# EDU_High-Speed-Design_CPU_HDMI.net
KiCad netlist of a schematic drawn in Altium Designer
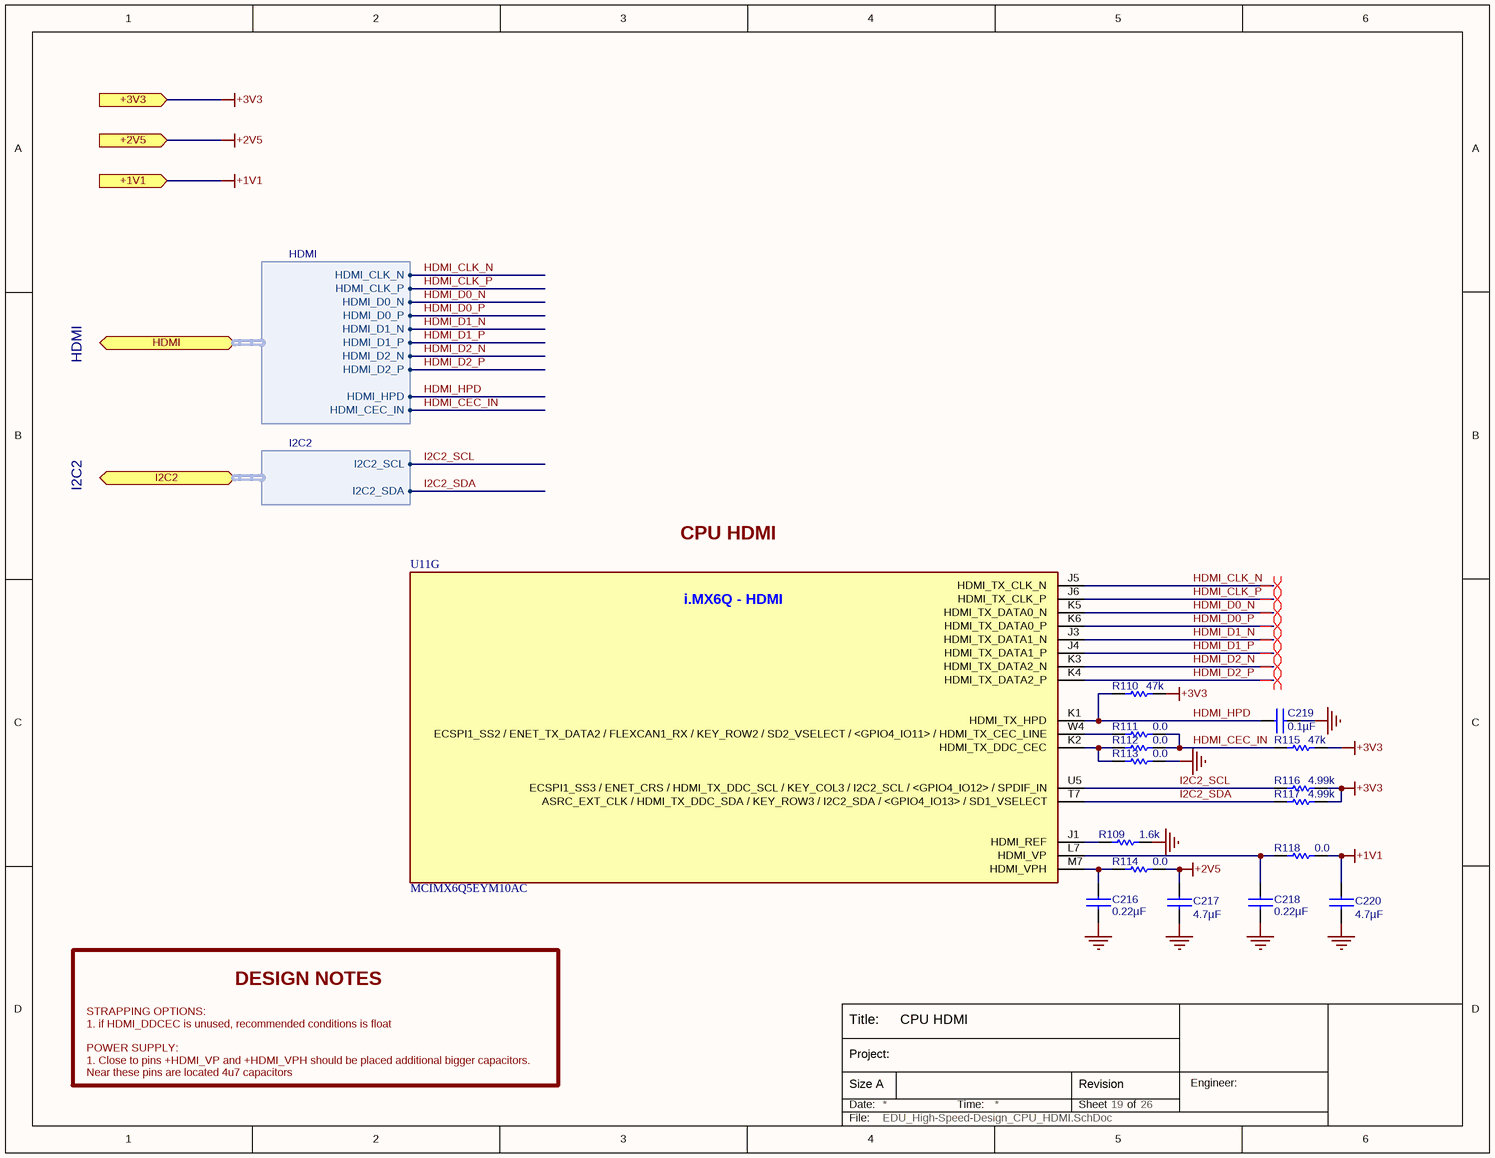
[diagram p0: EDU_High-Speed-Design_CPU_HDMI.SchDoc]

(export (version "E")
  (design (tool "Eeschema 10.0.6"))
  (components
    (comp (ref "C216")
      (value "0.22µF")
      (footprint "C0402")
      (description "CAP CER .22UF 25V X5R 20% 0402")
      (fields (field (name "VOLTAGE") "25V"))
      (libsource (lib "EDU_High-Speed-Design") (part "C1005X5R1E224M"))
    )
    (comp (ref "C217")
      (value "4.7µF")
      (footprint "C0402")
      (description "CAP CER 4.7UF 10V 20% X5R 0402")
      (fields (field (name "VOLTAGE") "10V"))
      (libsource (lib "EDU_High-Speed-Design") (part "C1005X5R1A475M"))
    )
    (comp (ref "C218")
      (value "0.22µF")
      (footprint "C0402")
      (description "CAP CER .22UF 25V X5R 20% 0402")
      (fields (field (name "VOLTAGE") "25V"))
      (libsource (lib "EDU_High-Speed-Design") (part "C1005X5R1E224M"))
    )
    (comp (ref "C219")
      (value "0.1µF")
      (footprint "C0402")
      (description "CAP CER .10UF 50V X5R 10% 0402")
      (fields (field (name "VOLTAGE") "50V"))
      (libsource (lib "EDU_High-Speed-Design") (part "C1005X5R1H104K"))
    )
    (comp (ref "C220")
      (value "4.7µF")
      (footprint "C0402")
      (description "CAP CER 4.7UF 10V 20% X5R 0402")
      (fields (field (name "VOLTAGE") "10V"))
      (libsource (lib "EDU_High-Speed-Design") (part "C1005X5R1A475M"))
    )
    (comp (ref "R109")
      (value "1.6k")
      (footprint "R0402")
      (description "RES 1.6K OHM 1/10W 1% 0402 SMD")
      (libsource (lib "EDU_High-Speed-Design") (part "ERJ-2RKF1601X"))
    )
    (comp (ref "R110")
      (value "47k")
      (footprint "R0402")
      (description "RES 47.0K OHM 1/16W 1% 0402 SMD")
      (fields
        (field (name "MANUFACTURER") "Yageo")
        (field (name "MANUFACTURER PART NUMBER") "RC0402FR-0747KL")
      )
      (libsource (lib "EDU_High-Speed-Design") (part "RC0402FR-0747KL"))
    )
    (comp (ref "R111")
      (value "0.0")
      (footprint "R0402")
      (description "RES 0.0 OHM 1/16W 0402 SMD")
      (libsource (lib "EDU_High-Speed-Design") (part "RC0402JR-070RL"))
    )
    (comp (ref "R112")
      (value "0.0")
      (footprint "R0402")
      (description "RES 0.0 OHM 1/16W 0402 SMD")
      (libsource (lib "EDU_High-Speed-Design") (part "RC0402JR-070RL"))
    )
    (comp (ref "R113")
      (value "0.0")
      (footprint "R0402")
      (description "RES 0.0 OHM 1/16W 0402 SMD")
      (libsource (lib "EDU_High-Speed-Design") (part "RC0402JR-070RL"))
    )
    (comp (ref "R114")
      (value "0.0")
      (footprint "R0402")
      (description "RES 0.0 OHM 1/16W 0402 SMD")
      (libsource (lib "EDU_High-Speed-Design") (part "RC0402JR-070RL"))
    )
    (comp (ref "R115")
      (value "47k")
      (footprint "R0402")
      (description "RES 47.0K OHM 1/16W 1% 0402 SMD")
      (fields
        (field (name "MANUFACTURER") "Yageo")
        (field (name "MANUFACTURER PART NUMBER") "RC0402FR-0747KL")
      )
      (libsource (lib "EDU_High-Speed-Design") (part "RC0402FR-0747KL"))
    )
    (comp (ref "R116")
      (value "4.99k")
      (footprint "R0402")
      (description "RES TF 4.99K OHM 1% 1/16W 0402")
      (libsource (lib "EDU_High-Speed-Design") (part "RMCF0402FT4K99"))
    )
    (comp (ref "R117")
      (value "4.99k")
      (footprint "R0402")
      (description "RES TF 4.99K OHM 1% 1/16W 0402")
      (libsource (lib "EDU_High-Speed-Design") (part "RMCF0402FT4K99"))
    )
    (comp (ref "R118")
      (value "0.0")
      (footprint "R0402")
      (description "RES 0.0 OHM 1/16W 0402 SMD")
      (libsource (lib "EDU_High-Speed-Design") (part "RC0402JR-070RL"))
    )
    (comp (ref "U11")
      (value "MCIMX6Q5EYM10AC")
      (footprint "MCIMX6Q5EYM10AC")
      (description "IC MCU 32BIT ARM QUAD 624FCBGA")
      (libsource (lib "EDU_High-Speed-Design") (part "MCIMX6Q5EYM10AC"))
    )
  )
  (nets
    (net (code "3") (name "+1V1") (class "Default")
      (node (ref "C220") (pin "1") (pinfunction "1_1") (pintype "passive"))
      (node (ref "R118") (pin "2") (pinfunction "2_2") (pintype "passive"))
    )
    (net (code "4") (name "+2V5") (class "Default")
      (node (ref "C217") (pin "1") (pinfunction "1_1") (pintype "passive"))
      (node (ref "R114") (pin "2") (pinfunction "2_2") (pintype "passive"))
    )
    (net (code "5") (name "+3V3") (class "Default")
      (node (ref "R110") (pin "1") (pinfunction "1_1") (pintype "passive"))
      (node (ref "R115") (pin "1") (pinfunction "1_1") (pintype "passive"))
      (node (ref "R116") (pin "1") (pinfunction "1_1") (pintype "passive"))
      (node (ref "R117") (pin "1") (pinfunction "1_1") (pintype "passive"))
    )
    (net (code "6") (name "/HDMI_CEC_IN") (class "Default")
      (node (ref "R111") (pin "1") (pinfunction "1_1") (pintype "passive"))
      (node (ref "R112") (pin "1") (pinfunction "1_1") (pintype "passive"))
      (node (ref "R115") (pin "2") (pinfunction "2_2") (pintype "passive"))
    )
    (net (code "7") (name "/HDMI_CLK_N") (class "Default")
      (node (ref "U11") (pin "J5") (pinfunction "HDMI_TX_CLK_N_J5") (pintype "passive"))
    )
    (net (code "8") (name "/HDMI_CLK_P") (class "Default")
      (node (ref "U11") (pin "J6") (pinfunction "HDMI_TX_CLK_P_J6") (pintype "passive"))
    )
    (net (code "9") (name "/HDMI_D0_N") (class "Default")
      (node (ref "U11") (pin "K5") (pinfunction "HDMI_TX_DATA0_N_K5") (pintype "passive"))
    )
    (net (code "10") (name "/HDMI_D0_P") (class "Default")
      (node (ref "U11") (pin "K6") (pinfunction "HDMI_TX_DATA0_P_K6") (pintype "passive"))
    )
    (net (code "11") (name "/HDMI_D1_N") (class "Default")
      (node (ref "U11") (pin "J3") (pinfunction "HDMI_TX_DATA1_N_J3") (pintype "passive"))
    )
    (net (code "12") (name "/HDMI_D1_P") (class "Default")
      (node (ref "U11") (pin "J4") (pinfunction "HDMI_TX_DATA1_P_J4") (pintype "passive"))
    )
    (net (code "13") (name "/HDMI_D2_N") (class "Default")
      (node (ref "U11") (pin "K3") (pinfunction "HDMI_TX_DATA2_N_K3") (pintype "passive"))
    )
    (net (code "14") (name "/HDMI_D2_P") (class "Default")
      (node (ref "U11") (pin "K4") (pinfunction "HDMI_TX_DATA2_P_K4") (pintype "passive"))
    )
    (net (code "15") (name "/HDMI_HPD") (class "Default")
      (node (ref "C219") (pin "1") (pinfunction "1_1") (pintype "passive"))
      (node (ref "R110") (pin "2") (pinfunction "2_2") (pintype "passive"))
      (node (ref "U11") (pin "K1") (pinfunction "HDMI_TX_HPD_K1") (pintype "passive"))
    )
    (net (code "16") (name "/I2C2_SCL") (class "Default")
      (node (ref "R116") (pin "2") (pinfunction "2_2") (pintype "passive"))
      (node (ref "U11") (pin "U5") (pinfunction "ECSPI1_SS3_/_ENET_CRS_/_HDMI_TX_DDC_SCL_/_KEY_COL3_/_I2C2_SCL_/_<GPIO4_IO12>_/_SPDIF_IN_U5") (pintype "passive"))
    )
    (net (code "17") (name "/I2C2_SDA") (class "Default")
      (node (ref "R117") (pin "2") (pinfunction "2_2") (pintype "passive"))
      (node (ref "U11") (pin "T7") (pinfunction "ASRC_EXT_CLK_/_HDMI_TX_DDC_SDA_/_KEY_ROW3_/_I2C2_SDA_/_<GPIO4_IO13>_/_SD1_VSELECT_T7") (pintype "passive"))
    )
    (net (code "20") (name "GND") (class "Default")
      (node (ref "C216") (pin "2") (pinfunction "2_2") (pintype "passive"))
      (node (ref "C217") (pin "2") (pinfunction "2_2") (pintype "passive"))
      (node (ref "C218") (pin "2") (pinfunction "2_2") (pintype "passive"))
      (node (ref "C219") (pin "2") (pinfunction "2_2") (pintype "passive"))
      (node (ref "C220") (pin "2") (pinfunction "2_2") (pintype "passive"))
      (node (ref "R109") (pin "1") (pinfunction "1_1") (pintype "passive"))
      (node (ref "R113") (pin "1") (pinfunction "1_1") (pintype "passive"))
    )
    (net (code "21") (name "Net-(U11G-ECSPI1_SS2_{slash}_ENET_TX_DATA2_{slash}_FLEXCAN1_RX_{slash}_KEY_ROW2_{slash}_SD2_VSELECT_{slash}_<GPIO4_IO11>_{slash}_HDMI_TX_CEC_LINE)") (class "Default")
      (node (ref "R111") (pin "2") (pinfunction "2_2") (pintype "passive"))
      (node (ref "U11") (pin "W4") (pinfunction "ECSPI1_SS2_/_ENET_TX_DATA2_/_FLEXCAN1_RX_/_KEY_ROW2_/_SD2_VSELECT_/_<GPIO4_IO11>_/_HDMI_TX_CEC_LINE_W4") (pintype "passive"))
    )
    (net (code "22") (name "Net-(U11G-HDMI_REF)") (class "Default")
      (node (ref "R109") (pin "2") (pinfunction "2_2") (pintype "passive"))
      (node (ref "U11") (pin "J1") (pinfunction "HDMI_REF_J1") (pintype "passive"))
    )
    (net (code "23") (name "Net-(U11G-HDMI_TX_DDC_CEC)") (class "Default")
      (node (ref "R112") (pin "2") (pinfunction "2_2") (pintype "passive"))
      (node (ref "R113") (pin "2") (pinfunction "2_2") (pintype "passive"))
      (node (ref "U11") (pin "K2") (pinfunction "HDMI_TX_DDC_CEC_K2") (pintype "passive"))
    )
    (net (code "24") (name "Net-(U11G-HDMI_VP)") (class "Default")
      (node (ref "C218") (pin "1") (pinfunction "1_1") (pintype "passive"))
      (node (ref "R118") (pin "1") (pinfunction "1_1") (pintype "passive"))
      (node (ref "U11") (pin "L7") (pinfunction "HDMI_VP_L7") (pintype "passive"))
    )
    (net (code "25") (name "Net-(U11G-HDMI_VPH)") (class "Default")
      (node (ref "C216") (pin "1") (pinfunction "1_1") (pintype "passive"))
      (node (ref "R114") (pin "1") (pinfunction "1_1") (pintype "passive"))
      (node (ref "U11") (pin "M7") (pinfunction "HDMI_VPH_M7") (pintype "passive"))
    )
  )
)
